# Output.net
KiCad netlist of a schematic drawn in Altium Designer
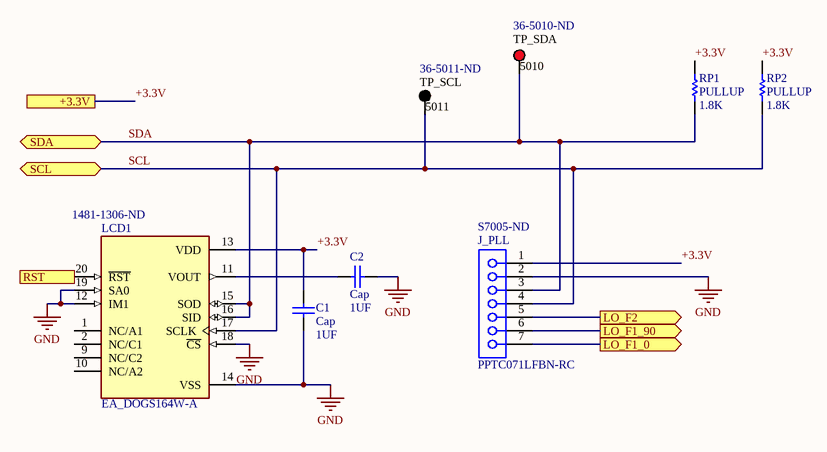
[diagram p0: Output.SchDoc]

(export (version "E")
  (design (tool "Eeschema 10.0.6"))
  (components
    (comp (ref "C1")
      (value "Cap")
      (footprint "RADIAL-0.1")
      (description "Capacitor")
      (fields
        (field (name "MANUFACTURER PART NUMBER") "ESE105M100AC3EA")
        (field (name "ALTIUM_VALUE") "1UF")
        (field (name "PUBLISHER") "Altium Limited")
      )
      (libsource (lib "ECE295-Capacitors-TH") (part "CAP ALUM 1UF 20% 100V RADIAL"))
    )
    (comp (ref "C2")
      (value "Cap")
      (footprint "RADIAL-0.1")
      (description "Capacitor")
      (fields
        (field (name "MANUFACTURER PART NUMBER") "ESE105M100AC3EA")
        (field (name "ALTIUM_VALUE") "1UF")
        (field (name "PUBLISHER") "Altium Limited")
      )
      (libsource (lib "ECE295-Capacitors-TH") (part "CAP ALUM 1UF 20% 100V RADIAL"))
    )
    (comp (ref "J_PLL")
      (value "PPTC071LFBN-RC")
      (footprint "SMTC-SSQ-107-01-X-S")
      (description "SQ Post Socket, Through-hole, Vertical, -55 to 125 degC, 2.54 mm Pitch, 7-Pin, Female, RoHS")
      (fields
        (field (name "PARTNUMBER") "SSQ-107-01-G-S")
        (field (name "MANUFACTURER") "Samtec")
        (field (name "SUPPLIER PART NUMBER 1") "S7005-ND")
      )
      (libsource (lib "Altium Content Vault") (part "SMTC-SSQ-107-01-X-S"))
    )
    (comp (ref "LCD1")
      (value "EA_DOGS164W-A")
      (footprint "LCD_EA_DOGS164W-A")
      (description "LCM char. 4x16 FSTN White Transflective EA DOGS164W-A")
      (fields
        (field (name "MF") "Display Visions")
        (field (name "MP") "EA DOGS164W-A")
        (field (name "SUPPLIER PART NUMBER 1") "1481-1306-ND")
      )
      (libsource (lib "EA_DOGS164W-A") (part "EA_DOGS164W-A"))
    )
    (comp (ref "RP1")
      (value "PULLUP")
      (footprint "AXIAL-0.1-RES")
      (description "Resistor")
      (fields
        (field (name "ALTIUM_VALUE") "1.8K")
        (field (name "MANUFACTURER PART NUMBER") "CFR-25JB-52-1K8")
        (field (name "TOLERANCE") "0.05")
        (field (name "PUBLISHER") "Altium Limited")
      )
      (libsource (lib "ECE295-Resistors-TH") (part "RES 1.8K OHM 5% 1/4W AXIAL"))
    )
    (comp (ref "RP2")
      (value "PULLUP")
      (footprint "AXIAL-0.1-RES")
      (description "Resistor")
      (fields
        (field (name "ALTIUM_VALUE") "1.8K")
        (field (name "MANUFACTURER PART NUMBER") "CFR-25JB-52-1K8")
        (field (name "TOLERANCE") "0.05")
        (field (name "PUBLISHER") "Altium Limited")
      )
      (libsource (lib "ECE295-Resistors-TH") (part "RES 1.8K OHM 5% 1/4W AXIAL"))
    )
    (comp (ref "TP_SCL")
      (value "5011")
      (footprint "KSTN-5011_V")
      (description "Interconnection Device")
      (fields (field (name "MANUFACTURER") "Keystone") (field (name "SUPPLIER PART NUMBER 1") "36-5011-ND"))
      (libsource (lib "Altium Content Vault") (part "TESTPOINT_BLACK"))
    )
    (comp (ref "TP_SDA")
      (value "5010")
      (footprint "KSTN-5010_V")
      (description "Interconnection Device")
      (fields (field (name "MANUFACTURER") "Keystone") (field (name "SUPPLIER PART NUMBER 1") "36-5010-ND"))
      (libsource (lib "Altium Content Vault") (part "TESTPOINT_RED"))
    )
  )
  (nets
    (net (code "1") (name "/+3.3V") (class "Default")
      (node (ref "C1") (pin "2") (pinfunction "2_2") (pintype "passive"))
      (node (ref "J_PLL") (pin "1") (pinfunction "1_1") (pintype "passive"))
      (node (ref "LCD1") (pin "13") (pinfunction "VDD_13") (pintype "power_in"))
      (node (ref "RP1") (pin "2") (pinfunction "2_2") (pintype "passive"))
      (node (ref "RP2") (pin "2") (pinfunction "2_2") (pintype "passive"))
    )
    (net (code "2") (name "/LO_F1_0") (class "Default")
      (node (ref "J_PLL") (pin "7") (pinfunction "7_7") (pintype "passive"))
    )
    (net (code "3") (name "/LO_F1_90") (class "Default")
      (node (ref "J_PLL") (pin "6") (pinfunction "6_6") (pintype "passive"))
    )
    (net (code "4") (name "/LO_F2") (class "Default")
      (node (ref "J_PLL") (pin "5") (pinfunction "5_5") (pintype "passive"))
    )
    (net (code "5") (name "/RST") (class "Default")
      (node (ref "LCD1") (pin "20") (pinfunction "~{RST}_20") (pintype "input"))
    )
    (net (code "6") (name "/SCL") (class "Default")
      (node (ref "J_PLL") (pin "4") (pinfunction "4_4") (pintype "passive"))
      (node (ref "LCD1") (pin "17") (pinfunction "SCLK_17") (pintype "input"))
      (node (ref "RP2") (pin "1") (pinfunction "1_1") (pintype "passive"))
      (node (ref "TP_SCL") (pin "1") (pinfunction "1_1") (pintype "passive"))
    )
    (net (code "7") (name "/SDA") (class "Default")
      (node (ref "J_PLL") (pin "3") (pinfunction "3_3") (pintype "passive"))
      (node (ref "LCD1") (pin "15") (pinfunction "SOD_15") (pintype "bidirectional"))
      (node (ref "LCD1") (pin "16") (pinfunction "SID_16") (pintype "bidirectional"))
      (node (ref "RP1") (pin "1") (pinfunction "1_1") (pintype "passive"))
      (node (ref "TP_SDA") (pin "1") (pinfunction "1_1") (pintype "passive"))
    )
    (net (code "8") (name "GND") (class "Default")
      (node (ref "C1") (pin "1") (pinfunction "1_1") (pintype "passive"))
      (node (ref "C2") (pin "1") (pinfunction "1_1") (pintype "passive"))
      (node (ref "J_PLL") (pin "2") (pinfunction "2_2") (pintype "passive"))
      (node (ref "LCD1") (pin "12") (pinfunction "IM1_12") (pintype "input"))
      (node (ref "LCD1") (pin "14") (pinfunction "VSS_14") (pintype "power_in"))
      (node (ref "LCD1") (pin "18") (pinfunction "~{CS}_18") (pintype "input"))
      (node (ref "LCD1") (pin "19") (pinfunction "SA0_19") (pintype "input"))
    )
    (net (code "9") (name "Net-(LCD1-VOUT)") (class "Default")
      (node (ref "C2") (pin "2") (pinfunction "2_2") (pintype "passive"))
      (node (ref "LCD1") (pin "11") (pinfunction "VOUT_11") (pintype "output"))
    )
    (net (code "10") (name "unconnected-(LCD1-NC{slash}A1-Pad1)") (class "Default")
      (node (ref "LCD1") (pin "1") (pinfunction "NC/A1_1") (pintype "passive"))
    )
    (net (code "11") (name "unconnected-(LCD1-NC{slash}A2-Pad10)") (class "Default")
      (node (ref "LCD1") (pin "10") (pinfunction "NC/A2_10") (pintype "passive"))
    )
    (net (code "12") (name "unconnected-(LCD1-NC{slash}C1-Pad2)") (class "Default")
      (node (ref "LCD1") (pin "2") (pinfunction "NC/C1_2") (pintype "passive"))
    )
    (net (code "13") (name "unconnected-(LCD1-NC{slash}C2-Pad9)") (class "Default")
      (node (ref "LCD1") (pin "9") (pinfunction "NC/C2_9") (pintype "passive"))
    )
  )
)
